# EC60_1.net
KiCad netlist of a schematic drawn in EAGLE
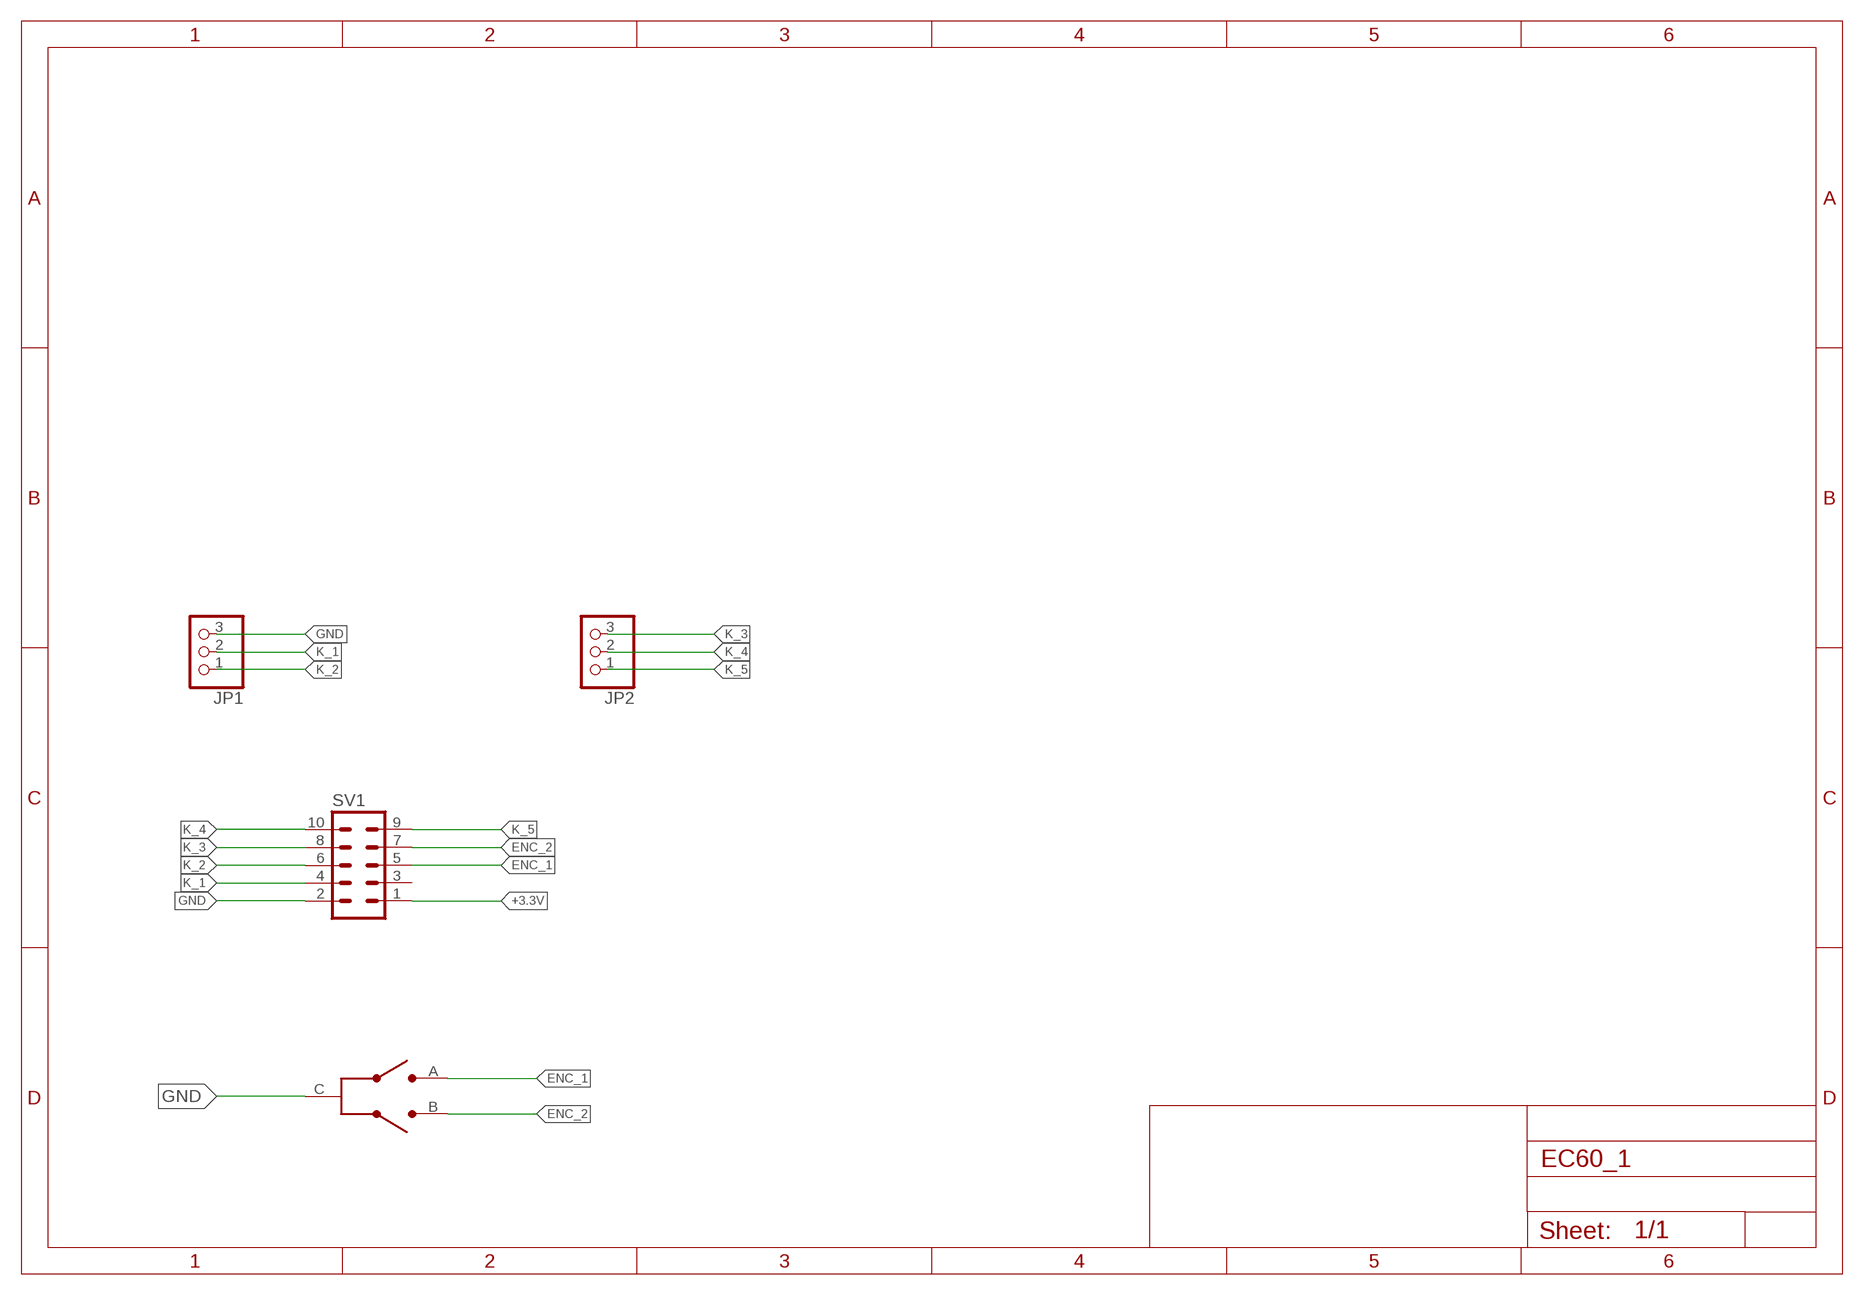
[diagram p0: schematic, sheet 1]

(export (version "E")
  (design (tool "Eeschema 10.0.6"))
  (components
    (comp (ref "JP1")
      (value "PINHD-1X3")
      (footprint "eagle-import:1X03")
      (libsource (lib "eagle-import") (part "PINHD-1X3"))
    )
    (comp (ref "JP2")
      (value "PINHD-1X3")
      (footprint "eagle-import:1X03")
      (libsource (lib "eagle-import") (part "PINHD-1X3"))
    )
    (comp (ref "SV1")
      (value "ML10L")
      (footprint "eagle-import:ML10L")
      (libsource (lib "eagle-import") (part "ML10L"))
    )
    (comp (ref "U$1")
      (value "EC60A")
      (footprint "eagle-import:EC60A")
      (libsource (lib "eagle-import") (part "EC60A"))
    )
  )
  (nets
    (net (code "1") (name "+3.3V") (class "Default")
      (node (ref "SV1") (pin "1") (pinfunction "1_1") (pintype "passive"))
    )
    (net (code "2") (name "ENC_1") (class "Default")
      (node (ref "SV1") (pin "5") (pinfunction "5_5") (pintype "passive"))
      (node (ref "U$1") (pin "A") (pinfunction "A_A") (pintype "passive"))
    )
    (net (code "3") (name "ENC_2") (class "Default")
      (node (ref "SV1") (pin "7") (pinfunction "7_7") (pintype "passive"))
      (node (ref "U$1") (pin "B") (pinfunction "B_B") (pintype "passive"))
    )
    (net (code "4") (name "GND") (class "Default")
      (node (ref "JP1") (pin "3") (pinfunction "3_3") (pintype "passive"))
      (node (ref "SV1") (pin "2") (pinfunction "2_2") (pintype "passive"))
      (node (ref "U$1") (pin "C") (pinfunction "C_C") (pintype "passive"))
    )
    (net (code "5") (name "K_1") (class "Default")
      (node (ref "JP1") (pin "2") (pinfunction "2_2") (pintype "passive"))
      (node (ref "SV1") (pin "4") (pinfunction "4_4") (pintype "passive"))
    )
    (net (code "6") (name "K_2") (class "Default")
      (node (ref "JP1") (pin "1") (pinfunction "1_1") (pintype "passive"))
      (node (ref "SV1") (pin "6") (pinfunction "6_6") (pintype "passive"))
    )
    (net (code "7") (name "K_3") (class "Default")
      (node (ref "JP2") (pin "3") (pinfunction "3_3") (pintype "passive"))
      (node (ref "SV1") (pin "8") (pinfunction "8_8") (pintype "passive"))
    )
    (net (code "8") (name "K_4") (class "Default")
      (node (ref "JP2") (pin "2") (pinfunction "2_2") (pintype "passive"))
      (node (ref "SV1") (pin "10") (pinfunction "10_10") (pintype "passive"))
    )
    (net (code "9") (name "K_5") (class "Default")
      (node (ref "JP2") (pin "1") (pinfunction "1_1") (pintype "passive"))
      (node (ref "SV1") (pin "9") (pinfunction "9_9") (pintype "passive"))
    )
    (net (code "10") (name "unconnected-(SV1-Pad3)") (class "Default")
      (node (ref "SV1") (pin "3") (pinfunction "3_3") (pintype "passive"))
    )
  )
)
